# AMX_audio30.net
KiCad netlist of a schematic drawn in Altium Designer
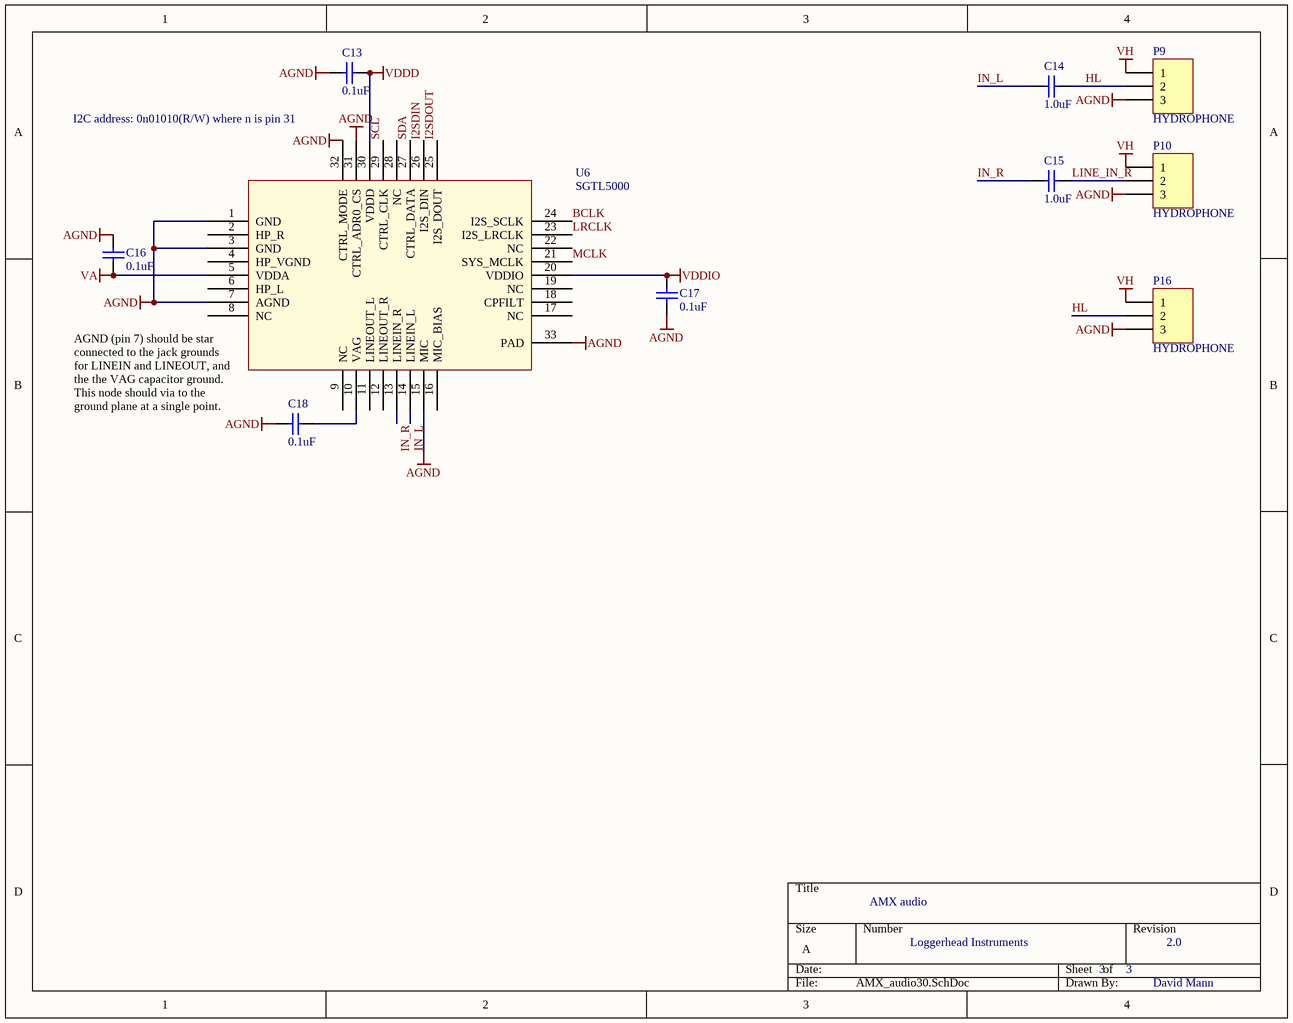
[diagram p0: AMX_audio30.SchDoc]

(export (version "E")
  (design (tool "Eeschema 10.0.6"))
  (components
    (comp (ref "C13")
      (value "0.1uF")
      (footprint "0402")
      (description "Ceramic Chip Capacitor - Standard")
      (fields (field (name "PUBLISHER") "Altium Limited"))
      (libsource (lib "KEMET Chip Capacitor") (part "C0402"))
    )
    (comp (ref "C14")
      (value "1.0uF")
      (footprint "0402")
      (description "Ceramic Chip Capacitor - Standard")
      (fields (field (name "PUBLISHER") "Altium Limited"))
      (libsource (lib "KEMET Chip Capacitor") (part "C0402"))
    )
    (comp (ref "C15")
      (value "1.0uF")
      (footprint "0402")
      (description "Ceramic Chip Capacitor - Standard")
      (fields (field (name "PUBLISHER") "Altium Limited"))
      (libsource (lib "KEMET Chip Capacitor") (part "C0402"))
    )
    (comp (ref "C16")
      (value "0.1uF")
      (footprint "0402")
      (description "Ceramic Chip Capacitor - Standard")
      (fields (field (name "PUBLISHER") "Altium Limited"))
      (libsource (lib "KEMET Chip Capacitor") (part "C0402"))
    )
    (comp (ref "C17")
      (value "0.1uF")
      (footprint "0402")
      (description "Ceramic Chip Capacitor - Standard")
      (fields (field (name "PUBLISHER") "Altium Limited"))
      (libsource (lib "KEMET Chip Capacitor") (part "C0402"))
    )
    (comp (ref "C18")
      (value "0.1uF")
      (footprint "0402")
      (description "Ceramic Chip Capacitor - Standard")
      (fields (field (name "PUBLISHER") "Altium Limited"))
      (libsource (lib "KEMET Chip Capacitor") (part "C0402"))
    )
    (comp (ref "P9")
      (value "HYDROPHONE")
      (footprint "HDR1X3")
      (description "Header, 3-Pin")
      (fields (field (name "PUBLISHER") "Altium Limited"))
      (libsource (lib "Miscellaneous Connectors") (part "Header 3"))
    )
    (comp (ref "P10")
      (value "HYDROPHONE")
      (footprint "HDR1X3")
      (description "Header, 3-Pin")
      (fields (field (name "PUBLISHER") "Altium Limited"))
      (libsource (lib "Miscellaneous Connectors") (part "Header 3"))
    )
    (comp (ref "P16")
      (value "HYDROPHONE")
      (footprint "HDR1X3")
      (description "Header, 3-Pin")
      (fields (field (name "PUBLISHER") "Altium Limited"))
      (libsource (lib "Miscellaneous Connectors") (part "Header 3"))
    )
    (comp (ref "U6") (value "SGTL5000") (footprint "QFN32") (libsource (lib "Loggerhead") (part "SGTL5000")))
  )
  (nets
    (net (code "1") (name "/BCLK") (class "Default")
      (node (ref "U6") (pin "24") (pinfunction "I2S_SCLK_24") (pintype "passive"))
    )
    (net (code "2") (name "/HL") (class "Default")
      (node (ref "C14") (pin "1") (pinfunction "1_1") (pintype "passive"))
      (node (ref "P16") (pin "2") (pinfunction "2_2") (pintype "passive"))
      (node (ref "P9") (pin "2") (pinfunction "2_2") (pintype "passive"))
    )
    (net (code "3") (name "/I2SDIN") (class "Default")
      (node (ref "U6") (pin "26") (pinfunction "I2S_DIN_26") (pintype "passive"))
    )
    (net (code "4") (name "/I2SDOUT") (class "Default")
      (node (ref "U6") (pin "25") (pinfunction "I2S_DOUT_25") (pintype "passive"))
    )
    (net (code "5") (name "/IN_L") (class "Default")
      (node (ref "C14") (pin "2") (pinfunction "2_2") (pintype "passive"))
      (node (ref "U6") (pin "14") (pinfunction "LINEIN_L_14") (pintype "passive"))
    )
    (net (code "6") (name "/IN_R") (class "Default")
      (node (ref "C15") (pin "2") (pinfunction "2_2") (pintype "passive"))
      (node (ref "U6") (pin "13") (pinfunction "LINEIN_R_13") (pintype "passive"))
    )
    (net (code "7") (name "/LINE_IN_R") (class "Default")
      (node (ref "C15") (pin "1") (pinfunction "1_1") (pintype "passive"))
      (node (ref "P10") (pin "2") (pinfunction "2_2") (pintype "passive"))
    )
    (net (code "8") (name "/LRCLK") (class "Default")
      (node (ref "U6") (pin "23") (pinfunction "I2S_LRCLK_23") (pintype "passive"))
    )
    (net (code "9") (name "/MCLK") (class "Default")
      (node (ref "U6") (pin "21") (pinfunction "SYS_MCLK_21") (pintype "passive"))
    )
    (net (code "10") (name "/SCL") (class "Default")
      (node (ref "U6") (pin "29") (pinfunction "CTRL_CLK_29") (pintype "passive"))
    )
    (net (code "11") (name "/SDA") (class "Default")
      (node (ref "U6") (pin "27") (pinfunction "CTRL_DATA_27") (pintype "passive"))
    )
    (net (code "12") (name "AGND") (class "Default")
      (node (ref "C13") (pin "2") (pinfunction "2_2") (pintype "passive"))
      (node (ref "C16") (pin "2") (pinfunction "2_2") (pintype "passive"))
      (node (ref "C17") (pin "2") (pinfunction "2_2") (pintype "passive"))
      (node (ref "C18") (pin "2") (pinfunction "2_2") (pintype "passive"))
      (node (ref "P10") (pin "3") (pinfunction "3_3") (pintype "passive"))
      (node (ref "P16") (pin "3") (pinfunction "3_3") (pintype "passive"))
      (node (ref "P9") (pin "3") (pinfunction "3_3") (pintype "passive"))
      (node (ref "U6") (pin "1") (pinfunction "GND_1") (pintype "passive"))
      (node (ref "U6") (pin "15") (pinfunction "MIC_15") (pintype "passive"))
      (node (ref "U6") (pin "3") (pinfunction "GND_3") (pintype "passive"))
      (node (ref "U6") (pin "31") (pinfunction "CTRL_ADR0_CS_31") (pintype "passive"))
      (node (ref "U6") (pin "32") (pinfunction "CTRL_MODE_32") (pintype "passive"))
      (node (ref "U6") (pin "33") (pinfunction "PAD_33") (pintype "passive"))
      (node (ref "U6") (pin "7") (pinfunction "AGND_7") (pintype "passive"))
    )
    (net (code "13") (name "Net-(U6-VAG)") (class "Default")
      (node (ref "C18") (pin "1") (pinfunction "1_1") (pintype "passive"))
      (node (ref "U6") (pin "10") (pinfunction "VAG_10") (pintype "passive"))
    )
    (net (code "14") (name "VA") (class "Default")
      (node (ref "C16") (pin "1") (pinfunction "1_1") (pintype "passive"))
      (node (ref "U6") (pin "5") (pinfunction "VDDA_5") (pintype "passive"))
    )
    (net (code "15") (name "VDDD") (class "Default")
      (node (ref "C13") (pin "1") (pinfunction "1_1") (pintype "passive"))
      (node (ref "U6") (pin "30") (pinfunction "VDDD_30") (pintype "passive"))
    )
    (net (code "16") (name "VDDIO") (class "Default")
      (node (ref "C17") (pin "1") (pinfunction "1_1") (pintype "passive"))
      (node (ref "U6") (pin "20") (pinfunction "VDDIO_20") (pintype "passive"))
    )
    (net (code "17") (name "VH") (class "Default")
      (node (ref "P10") (pin "1") (pinfunction "1_1") (pintype "passive"))
      (node (ref "P16") (pin "1") (pinfunction "1_1") (pintype "passive"))
      (node (ref "P9") (pin "1") (pinfunction "1_1") (pintype "passive"))
    )
    (net (code "18") (name "unconnected-(U6-CPFILT-Pad18)") (class "Default")
      (node (ref "U6") (pin "18") (pinfunction "CPFILT_18") (pintype "passive"))
    )
    (net (code "19") (name "unconnected-(U6-HP_L-Pad6)") (class "Default")
      (node (ref "U6") (pin "6") (pinfunction "HP_L_6") (pintype "passive"))
    )
    (net (code "20") (name "unconnected-(U6-HP_R-Pad2)") (class "Default")
      (node (ref "U6") (pin "2") (pinfunction "HP_R_2") (pintype "passive"))
    )
    (net (code "21") (name "unconnected-(U6-HP_VGND-Pad4)") (class "Default")
      (node (ref "U6") (pin "4") (pinfunction "HP_VGND_4") (pintype "passive"))
    )
    (net (code "22") (name "unconnected-(U6-LINEOUT_L-Pad11)") (class "Default")
      (node (ref "U6") (pin "11") (pinfunction "LINEOUT_L_11") (pintype "passive"))
    )
    (net (code "23") (name "unconnected-(U6-LINEOUT_R-Pad12)") (class "Default")
      (node (ref "U6") (pin "12") (pinfunction "LINEOUT_R_12") (pintype "passive"))
    )
    (net (code "24") (name "unconnected-(U6-MIC_BIAS-Pad16)") (class "Default")
      (node (ref "U6") (pin "16") (pinfunction "MIC_BIAS_16") (pintype "passive"))
    )
    (net (code "25") (name "unconnected-(U6-NC-Pad8)") (class "Default")
      (node (ref "U6") (pin "8") (pinfunction "NC_8") (pintype "passive"))
    )
    (net (code "26") (name "unconnected-(U6-NC-Pad9)") (class "Default")
      (node (ref "U6") (pin "9") (pinfunction "NC_9") (pintype "passive"))
    )
    (net (code "27") (name "unconnected-(U6-NC-Pad17)") (class "Default")
      (node (ref "U6") (pin "17") (pinfunction "NC_17") (pintype "passive"))
    )
    (net (code "28") (name "unconnected-(U6-NC-Pad19)") (class "Default")
      (node (ref "U6") (pin "19") (pinfunction "NC_19") (pintype "passive"))
    )
    (net (code "29") (name "unconnected-(U6-NC-Pad22)") (class "Default")
      (node (ref "U6") (pin "22") (pinfunction "NC_22") (pintype "passive"))
    )
    (net (code "30") (name "unconnected-(U6-NC-Pad28)") (class "Default")
      (node (ref "U6") (pin "28") (pinfunction "NC_28") (pintype "passive"))
    )
  )
)
